# motocontro_rev_4.net
KiCad netlist of a schematic drawn in EAGLE
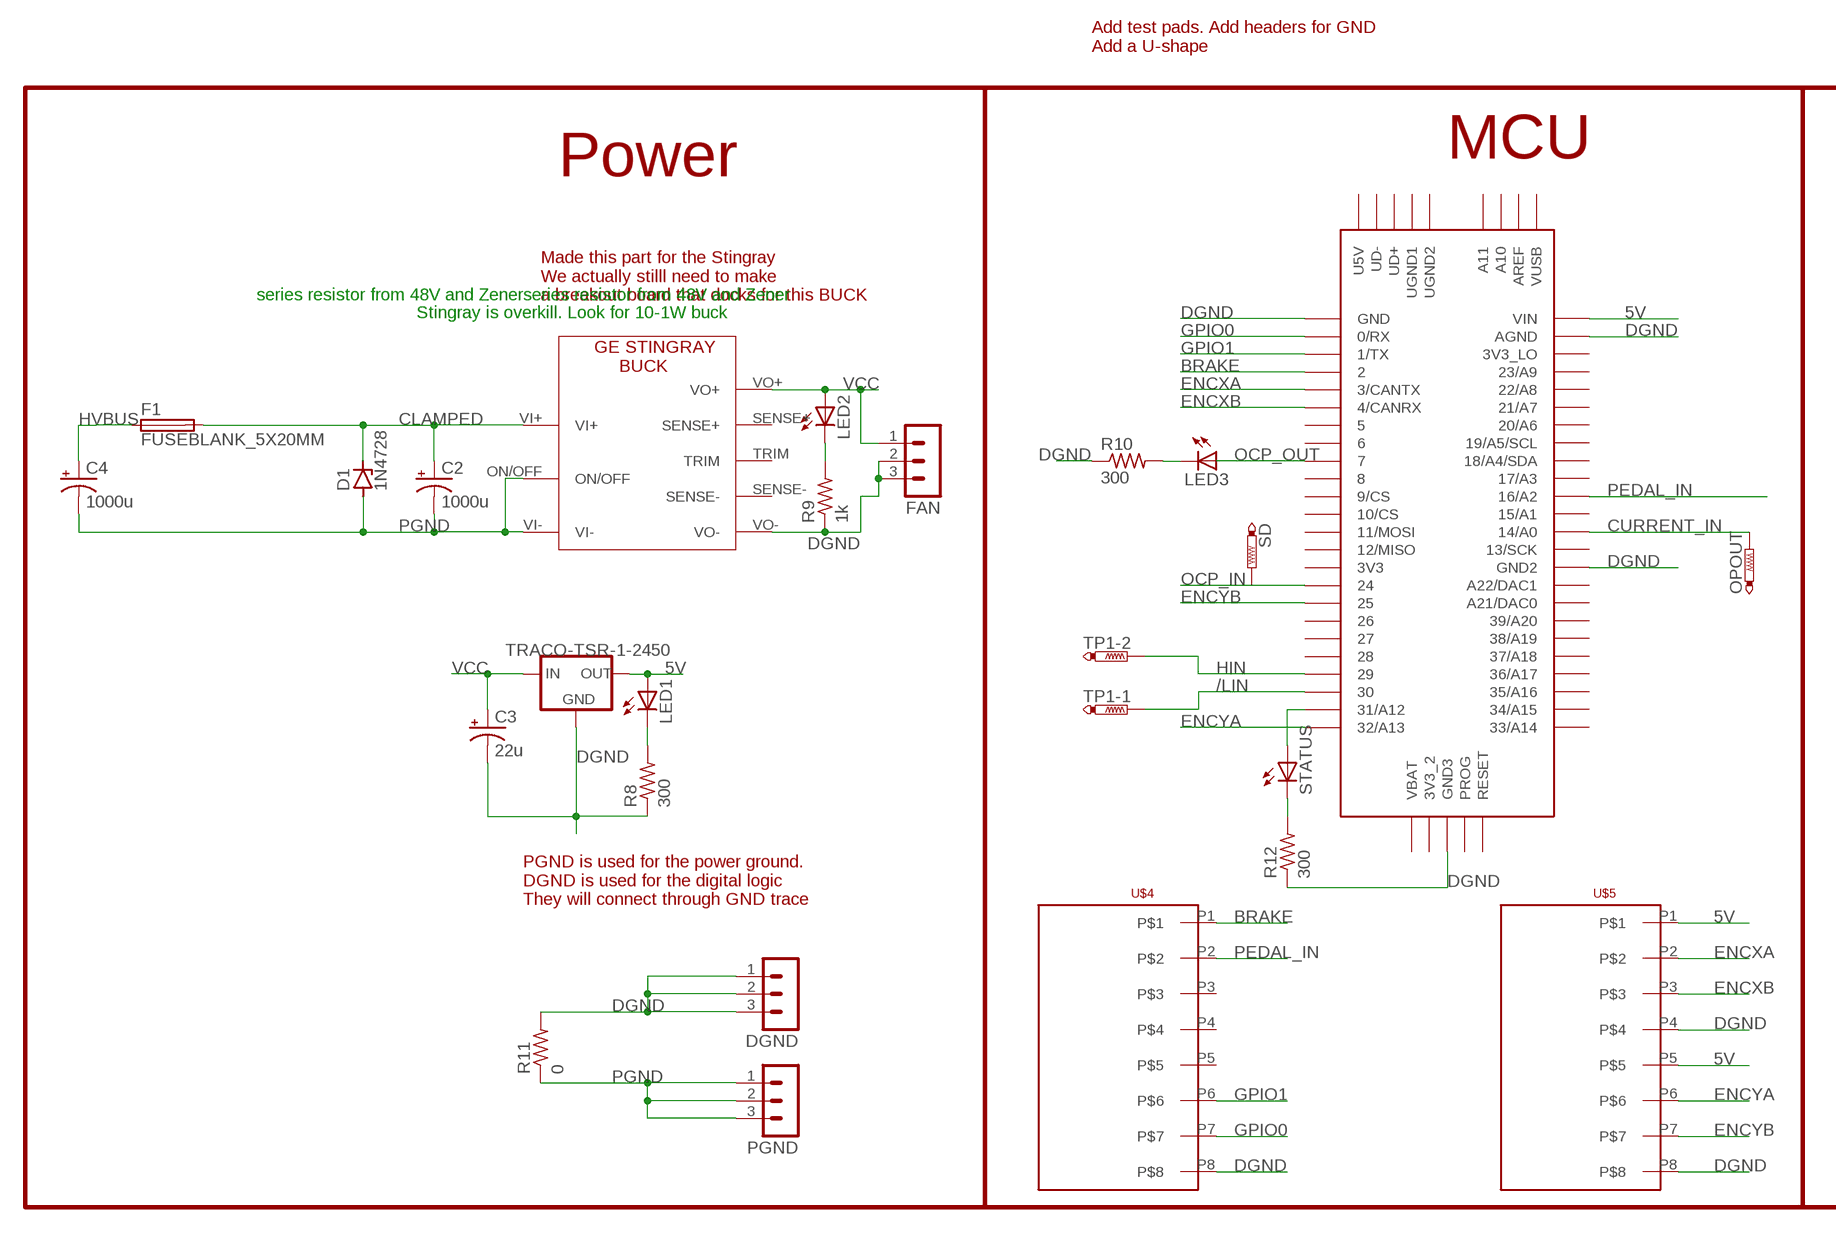
[diagram p0: schematic, sheet 1, part 1 of 2]
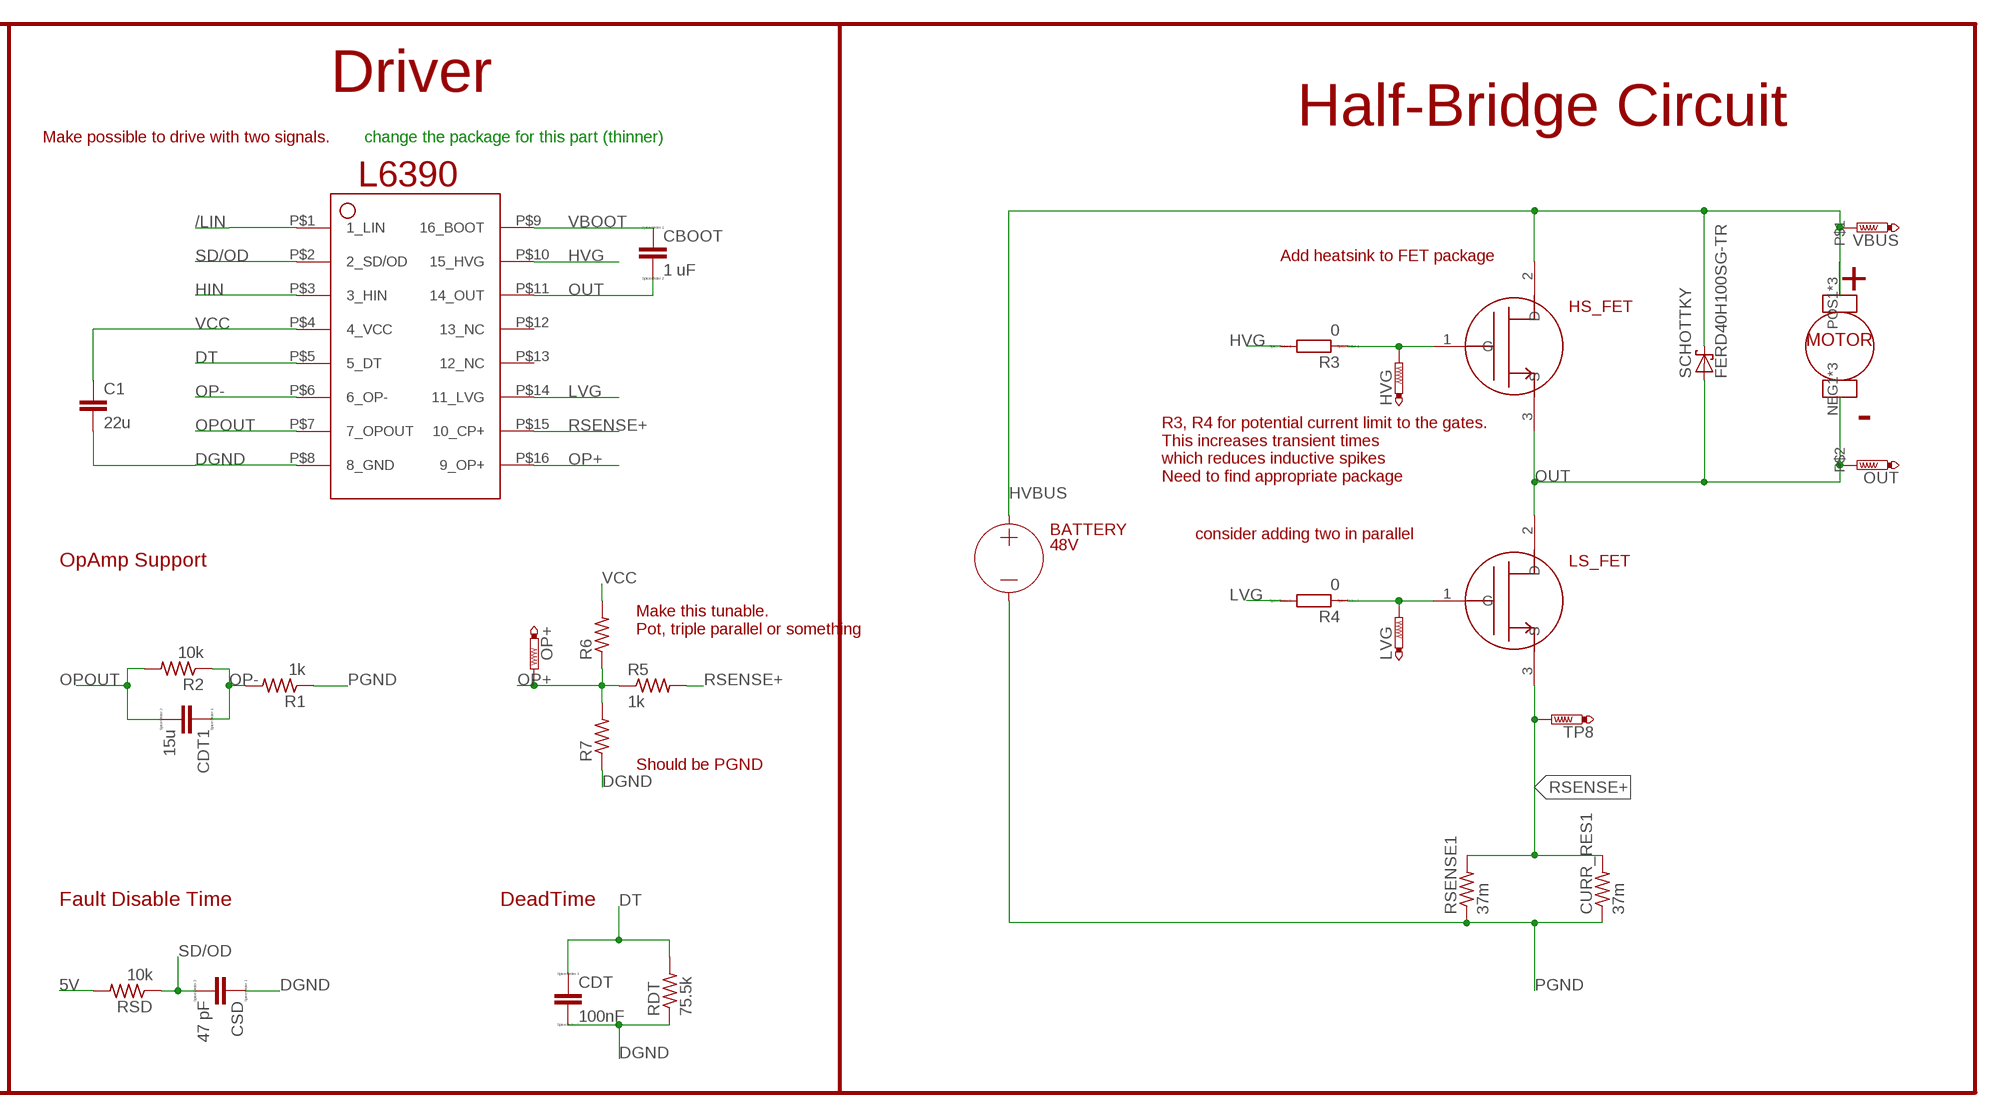
[diagram p1: schematic, sheet 1, part 2 of 2]

(export (version "E")
  (design (tool "Eeschema 10.0.6"))
  (components
    (comp (ref "BATTERY")
      (value "48V")
      (footprint "eagle-import:SB50POWER_CLAW")
      (libsource (lib "eagle-import") (part "BATTERY"))
    )
    (comp (ref "C1")
      (value "22u")
      (footprint "eagle-import:RESC0805_M")
      (libsource (lib "eagle-import") (part "CAPACITOR_0805_M"))
    )
    (comp (ref "C2")
      (value "1000u")
      (footprint "eagle-import:E5-13")
      (libsource (lib "eagle-import") (part "CPOL-USE5-13"))
    )
    (comp (ref "C3")
      (value "22u")
      (footprint "eagle-import:153CLV-0605")
      (libsource (lib "eagle-import") (part "adafruit_420_CPOL-US153CLV-0605"))
    )
    (comp (ref "C4")
      (value "1000u")
      (footprint "eagle-import:EB20D")
      (libsource (lib "eagle-import") (part "adafruit_420_CPOL-USE10-20"))
    )
    (comp (ref "CBOOT")
      (value "1 uF")
      (footprint "eagle-import:C1206")
      (libsource (lib "eagle-import") (part "CC1206"))
    )
    (comp (ref "CDT")
      (value "100nF")
      (footprint "eagle-import:C1206")
      (libsource (lib "eagle-import") (part "CC1206"))
    )
    (comp (ref "CDT1")
      (value "15u")
      (footprint "eagle-import:C1206")
      (libsource (lib "eagle-import") (part "CC1206"))
    )
    (comp (ref "CSD")
      (value "47 pF")
      (footprint "eagle-import:C1206")
      (libsource (lib "eagle-import") (part "CC1206"))
    )
    (comp (ref "CURR_RES1")
      (value "37m")
      (footprint "eagle-import:2818_WITH_VIA")
      (libsource (lib "eagle-import") (part "RESSENSE_2818"))
    )
    (comp (ref "D1")
      (value "1N4728")
      (footprint "eagle-import:DO41Z10")
      (libsource (lib "eagle-import") (part "1N4728"))
    )
    (comp (ref "DGND")
      (value "MA03-1")
      (footprint "eagle-import:MA03-1")
      (libsource (lib "eagle-import") (part "MA03-1"))
    )
    (comp (ref "F1")
      (value "FUSEBLANK_5X20MM")
      (footprint "eagle-import:FUSE_HOLDER_5X20MM")
      (libsource (lib "eagle-import") (part "FUSEBLANK_5X20MM"))
    )
    (comp (ref "FAN")
      (value "MA03-1")
      (footprint "eagle-import:MA03-1")
      (libsource (lib "eagle-import") (part "MA03-1"))
    )
    (comp (ref "HS_FET")
      (value "FDB86360_NFETTO263/D2PAK")
      (footprint "eagle-import:TO-263_D2PAK")
      (libsource (lib "eagle-import") (part "FDB86360_NFETTO263/D2PAK"))
    )
    (comp (ref "HVG")
      (value "PTR1B1,27")
      (footprint "eagle-import:B1,27")
      (libsource (lib "eagle-import") (part "PTR1B1,27"))
    )
    (comp (ref "LDO")
      (value "TRACO-TSR-1-2450")
      (footprint "eagle-import:SIP3")
      (libsource (lib "eagle-import") (part "TRACO-TSR-1-2450"))
    )
    (comp (ref "LED1")
      (value "LEDCHIP-LED0805")
      (footprint "eagle-import:CHIP-LED0805")
      (libsource (lib "eagle-import") (part "LEDCHIP-LED0805"))
    )
    (comp (ref "LED2")
      (value "LEDCHIP-LED0805")
      (footprint "eagle-import:CHIP-LED0805")
      (libsource (lib "eagle-import") (part "LEDCHIP-LED0805"))
    )
    (comp (ref "LED3")
      (value "LEDCHIP-LED0805")
      (footprint "eagle-import:CHIP-LED0805")
      (libsource (lib "eagle-import") (part "LEDCHIP-LED0805"))
    )
    (comp (ref "LS_FET")
      (value "FDB86360_NFETTO263/D2PAK")
      (footprint "eagle-import:TO-263_D2PAK")
      (libsource (lib "eagle-import") (part "FDB86360_NFETTO263/D2PAK"))
    )
    (comp (ref "LVG")
      (value "PTR1B1,27")
      (footprint "eagle-import:B1,27")
      (libsource (lib "eagle-import") (part "PTR1B1,27"))
    )
    (comp (ref "MOTOR")
      (value "MOTOR")
      (footprint "eagle-import:SB50POWER_CLAW")
      (libsource (lib "eagle-import") (part "MOTOR"))
    )
    (comp (ref "OP+")
      (value "PTR1B1,27")
      (footprint "eagle-import:B1,27")
      (libsource (lib "eagle-import") (part "PTR1B1,27"))
    )
    (comp (ref "OPOUT")
      (value "PTR1B1,27")
      (footprint "eagle-import:B1,27")
      (libsource (lib "eagle-import") (part "PTR1B1,27"))
    )
    (comp (ref "OUT")
      (value "PTR1B1,27")
      (footprint "eagle-import:B1,27")
      (libsource (lib "eagle-import") (part "PTR1B1,27"))
    )
    (comp (ref "PGND")
      (value "MA03-1")
      (footprint "eagle-import:MA03-1")
      (libsource (lib "eagle-import") (part "MA03-1"))
    )
    (comp (ref "R1")
      (value "1k")
      (footprint "eagle-import:R0805")
      (libsource (lib "eagle-import") (part "R-US_R0805"))
    )
    (comp (ref "R2")
      (value "10k")
      (footprint "eagle-import:R0805")
      (libsource (lib "eagle-import") (part "R-US_R0805"))
    )
    (comp (ref "R3")
      (value "0")
      (footprint "eagle-import:R2012")
      (libsource (lib "eagle-import") (part "RR2012"))
    )
    (comp (ref "R4")
      (value "0")
      (footprint "eagle-import:R2012")
      (libsource (lib "eagle-import") (part "RR2012"))
    )
    (comp (ref "R5")
      (value "1k")
      (footprint "eagle-import:R0805")
      (libsource (lib "eagle-import") (part "R-US_R0805"))
    )
    (comp (ref "R6")
      (value "R-US_R0805")
      (footprint "eagle-import:R0805")
      (libsource (lib "eagle-import") (part "R-US_R0805"))
    )
    (comp (ref "R7")
      (value "R-US_R0805")
      (footprint "eagle-import:R0805")
      (libsource (lib "eagle-import") (part "R-US_R0805"))
    )
    (comp (ref "R8")
      (value "300")
      (footprint "eagle-import:R0805")
      (libsource (lib "eagle-import") (part "R-US_R0805"))
    )
    (comp (ref "R9")
      (value "1k")
      (footprint "eagle-import:R0805")
      (libsource (lib "eagle-import") (part "R-US_R0805"))
    )
    (comp (ref "R10")
      (value "300")
      (footprint "eagle-import:R0805")
      (libsource (lib "eagle-import") (part "R-US_R0805"))
    )
    (comp (ref "R11")
      (value "0")
      (footprint "eagle-import:R0805")
      (libsource (lib "eagle-import") (part "R-US_R0805"))
    )
    (comp (ref "R12")
      (value "300")
      (footprint "eagle-import:R0805")
      (libsource (lib "eagle-import") (part "R-US_R0805"))
    )
    (comp (ref "RDT")
      (value "75.5k")
      (footprint "eagle-import:R0805")
      (libsource (lib "eagle-import") (part "R-US_R0805"))
    )
    (comp (ref "RSD")
      (value "10k")
      (footprint "eagle-import:R0805")
      (libsource (lib "eagle-import") (part "R-US_R0805"))
    )
    (comp (ref "RSENSE1")
      (value "37m")
      (footprint "eagle-import:2818_WITH_VIA")
      (libsource (lib "eagle-import") (part "RESSENSE_2818"))
    )
    (comp (ref "SCHOTTKY")
      (value "FERD40H100SG-TR")
      (footprint "eagle-import:TO-263_D2PAK")
      (libsource (lib "eagle-import") (part "FERD40H100SG-TR"))
    )
    (comp (ref "SD")
      (value "PTR1B1,27")
      (footprint "eagle-import:B1,27")
      (libsource (lib "eagle-import") (part "PTR1B1,27"))
    )
    (comp (ref "STATUS")
      (value "LEDCHIP-LED0805")
      (footprint "eagle-import:CHIP-LED0805")
      (libsource (lib "eagle-import") (part "LEDCHIP-LED0805"))
    )
    (comp (ref "TP1")
      (value "PTR2")
      (footprint "eagle-import:P2-38-17")
      (libsource (lib "eagle-import") (part "PTR2"))
    )
    (comp (ref "TP8")
      (value "PTR1B1,27")
      (footprint "eagle-import:B1,27")
      (libsource (lib "eagle-import") (part "PTR1B1,27"))
    )
    (comp (ref "U$1")
      (value "L6390SO-16NARRROW")
      (footprint "eagle-import:SO-16NARROW")
      (libsource (lib "eagle-import") (part "L6390SO-16NARRROW"))
    )
    (comp (ref "U$2")
      (value "TEENSY_3.5/3.6")
      (footprint "eagle-import:TEENSY_3.5_3.6")
      (libsource (lib "eagle-import") (part "TEENSY_3.5/3.6"))
    )
    (comp (ref "U$3")
      (value "GE_STINGRAY_H")
      (footprint "eagle-import:GE_STINGRAY")
      (libsource (lib "eagle-import") (part "GE_STINGRAY_H"))
    )
    (comp (ref "U$4")
      (value "8-PIN-MOLEX-RA-FEMALE")
      (footprint "eagle-import:8-PIN-MOLEX")
      (libsource (lib "eagle-import") (part "8-PIN-MOLEX-RA-FEMALE"))
    )
    (comp (ref "U$5")
      (value "8-PIN-MOLEX-RA-FEMALE")
      (footprint "eagle-import:8-PIN-MOLEX")
      (libsource (lib "eagle-import") (part "8-PIN-MOLEX-RA-FEMALE"))
    )
    (comp (ref "VBUS")
      (value "PTR1B1,27")
      (footprint "eagle-import:B1,27")
      (libsource (lib "eagle-import") (part "PTR1B1,27"))
    )
  )
  (nets
    (net (code "1") (name "/5V") (class "Default")
      (node (ref "LDO") (pin "3") (pinfunction "OUT_3") (pintype "passive"))
      (node (ref "LED1") (pin "A") (pinfunction "A_A") (pintype "passive"))
      (node (ref "RSD") (pin "2") (pinfunction "2_2") (pintype "passive"))
      (node (ref "U$2") (pin "VIN") (pinfunction "VIN_VIN") (pintype "bidirectional"))
      (node (ref "U$5") (pin "P1") (pinfunction "P$1_P1") (pintype "bidirectional"))
      (node (ref "U$5") (pin "P5") (pinfunction "P$5_P5") (pintype "bidirectional"))
    )
    (net (code "2") (name "/BRAKE") (class "Default")
      (node (ref "U$2") (pin "2") (pinfunction "2_2") (pintype "bidirectional"))
      (node (ref "U$4") (pin "P1") (pinfunction "P$1_P1") (pintype "bidirectional"))
    )
    (net (code "3") (name "/CLAMPED") (class "Default")
      (node (ref "C2") (pin "+") (pinfunction "+_+") (pintype "passive"))
      (node (ref "D1") (pin "C") (pinfunction "C_C") (pintype "passive"))
      (node (ref "F1") (pin "2") (pinfunction "2_2") (pintype "passive"))
      (node (ref "U$3") (pin "VI+") (pinfunction "VI+_VI+") (pintype "bidirectional"))
    )
    (net (code "4") (name "/CURRENT_IN") (class "Default")
      (node (ref "OPOUT") (pin "TP") (pinfunction "TP_TP") (pintype "input"))
      (node (ref "U$2") (pin "14/A0") (pinfunction "14/A0_14/A0") (pintype "bidirectional"))
    )
    (net (code "5") (name "/DGND") (class "Default")
      (node (ref "C1") (pin "2") (pinfunction "2_2") (pintype "passive"))
      (node (ref "C3") (pin "-") (pinfunction "-_-") (pintype "passive"))
      (node (ref "CDT") (pin "2") (pinfunction "2_2") (pintype "passive"))
      (node (ref "CSD") (pin "1") (pinfunction "1_1") (pintype "passive"))
      (node (ref "DGND") (pin "1") (pinfunction "1_1") (pintype "passive"))
      (node (ref "DGND") (pin "2") (pinfunction "2_2") (pintype "passive"))
      (node (ref "DGND") (pin "3") (pinfunction "3_3") (pintype "passive"))
      (node (ref "FAN") (pin "2") (pinfunction "2_2") (pintype "passive"))
      (node (ref "FAN") (pin "3") (pinfunction "3_3") (pintype "passive"))
      (node (ref "LDO") (pin "2") (pinfunction "GND_2") (pintype "input"))
      (node (ref "R10") (pin "1") (pinfunction "1_1") (pintype "passive"))
      (node (ref "R11") (pin "2") (pinfunction "2_2") (pintype "passive"))
      (node (ref "R12") (pin "1") (pinfunction "1_1") (pintype "passive"))
      (node (ref "R7") (pin "1") (pinfunction "1_1") (pintype "passive"))
      (node (ref "R8") (pin "1") (pinfunction "1_1") (pintype "passive"))
      (node (ref "R9") (pin "1") (pinfunction "1_1") (pintype "passive"))
      (node (ref "RDT") (pin "1") (pinfunction "1_1") (pintype "passive"))
      (node (ref "U$1") (pin "P$8") (pinfunction "8_GND_P$8") (pintype "bidirectional"))
      (node (ref "U$2") (pin "AGND") (pinfunction "AGND_AGND") (pintype "bidirectional"))
      (node (ref "U$2") (pin "GND") (pinfunction "GND_GND") (pintype "bidirectional"))
      (node (ref "U$2") (pin "GND2") (pinfunction "GND2_GND2") (pintype "bidirectional"))
      (node (ref "U$2") (pin "GND3") (pinfunction "GND3_GND3") (pintype "bidirectional"))
      (node (ref "U$3") (pin "VO-") (pinfunction "VO-_VO-") (pintype "bidirectional"))
      (node (ref "U$4") (pin "P8") (pinfunction "P$8_P8") (pintype "bidirectional"))
      (node (ref "U$5") (pin "P4") (pinfunction "P$4_P4") (pintype "bidirectional"))
      (node (ref "U$5") (pin "P8") (pinfunction "P$8_P8") (pintype "bidirectional"))
    )
    (net (code "6") (name "/DT") (class "Default")
      (node (ref "CDT") (pin "1") (pinfunction "1_1") (pintype "passive"))
      (node (ref "RDT") (pin "2") (pinfunction "2_2") (pintype "passive"))
      (node (ref "U$1") (pin "P$5") (pinfunction "5_DT_P$5") (pintype "bidirectional"))
    )
    (net (code "7") (name "/ENCXA") (class "Default")
      (node (ref "U$2") (pin "3/CANTX") (pinfunction "3/CANTX_3/CANTX") (pintype "bidirectional"))
      (node (ref "U$5") (pin "P2") (pinfunction "P$2_P2") (pintype "bidirectional"))
    )
    (net (code "8") (name "/ENCXB") (class "Default")
      (node (ref "U$2") (pin "4/CANRX") (pinfunction "4/CANRX_4/CANRX") (pintype "bidirectional"))
      (node (ref "U$5") (pin "P3") (pinfunction "P$3_P3") (pintype "bidirectional"))
    )
    (net (code "9") (name "/ENCYA") (class "Default")
      (node (ref "U$2") (pin "32/A13") (pinfunction "32/A13_32/A13") (pintype "bidirectional"))
      (node (ref "U$5") (pin "P6") (pinfunction "P$6_P6") (pintype "bidirectional"))
    )
    (net (code "10") (name "/ENCYB") (class "Default")
      (node (ref "U$2") (pin "25") (pinfunction "25_25") (pintype "bidirectional"))
      (node (ref "U$5") (pin "P7") (pinfunction "P$7_P7") (pintype "bidirectional"))
    )
    (net (code "11") (name "/GPIO0") (class "Default")
      (node (ref "U$2") (pin "0/RX") (pinfunction "0/RX_0/RX") (pintype "bidirectional"))
      (node (ref "U$4") (pin "P7") (pinfunction "P$7_P7") (pintype "bidirectional"))
    )
    (net (code "12") (name "/GPIO1") (class "Default")
      (node (ref "U$2") (pin "1/TX") (pinfunction "1/TX_1/TX") (pintype "bidirectional"))
      (node (ref "U$4") (pin "P6") (pinfunction "P$6_P6") (pintype "bidirectional"))
    )
    (net (code "13") (name "/HIN") (class "Default")
      (node (ref "TP1") (pin "TP-2") (pinfunction "TP_TP-2") (pintype "input"))
      (node (ref "U$1") (pin "P$3") (pinfunction "3_HIN_P$3") (pintype "bidirectional"))
      (node (ref "U$2") (pin "29") (pinfunction "29_29") (pintype "bidirectional"))
    )
    (net (code "14") (name "/HVBUS") (class "Default")
      (node (ref "BATTERY") (pin "POS1") (pinfunction "+_POS1") (pintype "passive"))
      (node (ref "BATTERY") (pin "POS2") (pinfunction "+_POS2") (pintype "passive"))
      (node (ref "BATTERY") (pin "POS3") (pinfunction "+_POS3") (pintype "passive"))
      (node (ref "C4") (pin "+") (pinfunction "+_+") (pintype "passive"))
      (node (ref "F1") (pin "1") (pinfunction "1_1") (pintype "passive"))
      (node (ref "HS_FET") (pin "2") (pinfunction "D_2") (pintype "bidirectional"))
      (node (ref "MOTOR") (pin "POS1") (pinfunction "P$1_POS1") (pintype "bidirectional"))
      (node (ref "MOTOR") (pin "POS2") (pinfunction "P$1_POS2") (pintype "bidirectional"))
      (node (ref "MOTOR") (pin "POS3") (pinfunction "P$1_POS3") (pintype "bidirectional"))
      (node (ref "SCHOTTKY") (pin "2") (pinfunction "C_2") (pintype "passive"))
      (node (ref "VBUS") (pin "TP") (pinfunction "TP_TP") (pintype "input"))
    )
    (net (code "15") (name "/HVG") (class "Default")
      (node (ref "R3") (pin "2") (pinfunction "2_2") (pintype "passive"))
      (node (ref "U$1") (pin "P$10") (pinfunction "15_HVG_P$10") (pintype "bidirectional"))
    )
    (net (code "16") (name "/LVG") (class "Default")
      (node (ref "R4") (pin "2") (pinfunction "2_2") (pintype "passive"))
      (node (ref "U$1") (pin "P$14") (pinfunction "11_LVG_P$14") (pintype "bidirectional"))
    )
    (net (code "17") (name "/OCP_IN") (class "Default")
      (node (ref "SD") (pin "TP") (pinfunction "TP_TP") (pintype "input"))
      (node (ref "U$2") (pin "24") (pinfunction "24_24") (pintype "bidirectional"))
    )
    (net (code "18") (name "/OCP_OUT") (class "Default")
      (node (ref "LED3") (pin "A") (pinfunction "A_A") (pintype "passive"))
      (node (ref "U$2") (pin "7") (pinfunction "7_7") (pintype "bidirectional"))
    )
    (net (code "19") (name "/OP+") (class "Default")
      (node (ref "OP+") (pin "TP") (pinfunction "TP_TP") (pintype "input"))
      (node (ref "R5") (pin "1") (pinfunction "1_1") (pintype "passive"))
      (node (ref "R6") (pin "1") (pinfunction "1_1") (pintype "passive"))
      (node (ref "R7") (pin "2") (pinfunction "2_2") (pintype "passive"))
      (node (ref "U$1") (pin "P$16") (pinfunction "9_OP+_P$16") (pintype "bidirectional"))
    )
    (net (code "20") (name "/OP-") (class "Default")
      (node (ref "CDT1") (pin "1") (pinfunction "1_1") (pintype "passive"))
      (node (ref "R1") (pin "2") (pinfunction "2_2") (pintype "passive"))
      (node (ref "R2") (pin "1") (pinfunction "1_1") (pintype "passive"))
      (node (ref "U$1") (pin "P$6") (pinfunction "6_OP-_P$6") (pintype "bidirectional"))
    )
    (net (code "21") (name "/OPOUT") (class "Default")
      (node (ref "CDT1") (pin "2") (pinfunction "2_2") (pintype "passive"))
      (node (ref "R2") (pin "2") (pinfunction "2_2") (pintype "passive"))
      (node (ref "U$1") (pin "P$7") (pinfunction "7_OPOUT_P$7") (pintype "bidirectional"))
    )
    (net (code "22") (name "/OUT") (class "Default")
      (node (ref "CBOOT") (pin "2") (pinfunction "2_2") (pintype "passive"))
      (node (ref "HS_FET") (pin "3") (pinfunction "S_3") (pintype "bidirectional"))
      (node (ref "LS_FET") (pin "2") (pinfunction "D_2") (pintype "bidirectional"))
      (node (ref "MOTOR") (pin "NEG1") (pinfunction "P$2_NEG1") (pintype "bidirectional"))
      (node (ref "MOTOR") (pin "NEG2") (pinfunction "P$2_NEG2") (pintype "bidirectional"))
      (node (ref "MOTOR") (pin "NEG3") (pinfunction "P$2_NEG3") (pintype "bidirectional"))
      (node (ref "OUT") (pin "TP") (pinfunction "TP_TP") (pintype "input"))
      (node (ref "SCHOTTKY") (pin "3") (pinfunction "A_3") (pintype "passive"))
      (node (ref "U$1") (pin "P$11") (pinfunction "14_OUT_P$11") (pintype "bidirectional"))
    )
    (net (code "23") (name "/PEDAL_IN") (class "Default")
      (node (ref "U$2") (pin "16/A2") (pinfunction "16/A2_16/A2") (pintype "bidirectional"))
      (node (ref "U$4") (pin "P2") (pinfunction "P$2_P2") (pintype "bidirectional"))
    )
    (net (code "24") (name "/PGND") (class "Default")
      (node (ref "BATTERY") (pin "NEG1") (pinfunction "-_NEG1") (pintype "passive"))
      (node (ref "BATTERY") (pin "NEG2") (pinfunction "-_NEG2") (pintype "passive"))
      (node (ref "BATTERY") (pin "NEG3") (pinfunction "-_NEG3") (pintype "passive"))
      (node (ref "C2") (pin "-") (pinfunction "-_-") (pintype "passive"))
      (node (ref "C4") (pin "-") (pinfunction "-_-") (pintype "passive"))
      (node (ref "CURR_RES1") (pin "P$1") (pinfunction "1_P$1") (pintype "passive"))
      (node (ref "CURR_RES1") (pin "P1.1") (pinfunction "1_P1.1") (pintype "passive"))
      (node (ref "D1") (pin "A") (pinfunction "A_A") (pintype "passive"))
      (node (ref "PGND") (pin "1") (pinfunction "1_1") (pintype "passive"))
      (node (ref "PGND") (pin "2") (pinfunction "2_2") (pintype "passive"))
      (node (ref "PGND") (pin "3") (pinfunction "3_3") (pintype "passive"))
      (node (ref "R1") (pin "1") (pinfunction "1_1") (pintype "passive"))
      (node (ref "R11") (pin "1") (pinfunction "1_1") (pintype "passive"))
      (node (ref "RSENSE1") (pin "P$1") (pinfunction "1_P$1") (pintype "passive"))
      (node (ref "RSENSE1") (pin "P1.1") (pinfunction "1_P1.1") (pintype "passive"))
      (node (ref "U$3") (pin "ON/OFF") (pinfunction "ON/OFF_ON/OFF") (pintype "bidirectional"))
      (node (ref "U$3") (pin "VI-") (pinfunction "VI-_VI-") (pintype "bidirectional"))
    )
    (net (code "25") (name "/SD{slash}OD") (class "Default")
      (node (ref "CSD") (pin "2") (pinfunction "2_2") (pintype "passive"))
      (node (ref "RSD") (pin "1") (pinfunction "1_1") (pintype "passive"))
      (node (ref "U$1") (pin "P$2") (pinfunction "2_SD/OD_P$2") (pintype "bidirectional"))
    )
    (net (code "26") (name "/VBOOT") (class "Default")
      (node (ref "CBOOT") (pin "1") (pinfunction "1_1") (pintype "passive"))
      (node (ref "U$1") (pin "P$9") (pinfunction "16_BOOT_P$9") (pintype "bidirectional"))
    )
    (net (code "27") (name "/VCC") (class "Default")
      (node (ref "C1") (pin "1") (pinfunction "1_1") (pintype "passive"))
      (node (ref "C3") (pin "+") (pinfunction "+_+") (pintype "passive"))
      (node (ref "FAN") (pin "1") (pinfunction "1_1") (pintype "passive"))
      (node (ref "LDO") (pin "1") (pinfunction "IN_1") (pintype "input"))
      (node (ref "LED2") (pin "A") (pinfunction "A_A") (pintype "passive"))
      (node (ref "R6") (pin "2") (pinfunction "2_2") (pintype "passive"))
      (node (ref "U$1") (pin "P$4") (pinfunction "4_VCC_P$4") (pintype "bidirectional"))
      (node (ref "U$3") (pin "VO+") (pinfunction "VO+_VO+") (pintype "bidirectional"))
    )
    (net (code "28") (name "/{slash}LIN") (class "Default")
      (node (ref "TP1") (pin "TP-1") (pinfunction "TP_TP-1") (pintype "input"))
      (node (ref "U$1") (pin "P$1") (pinfunction "1_LIN_P$1") (pintype "bidirectional"))
      (node (ref "U$2") (pin "30") (pinfunction "30_30") (pintype "bidirectional"))
    )
    (net (code "29") (name "Net-(HS_FET-G)") (class "Default")
      (node (ref "HS_FET") (pin "1") (pinfunction "G_1") (pintype "bidirectional"))
      (node (ref "HVG") (pin "TP") (pinfunction "TP_TP") (pintype "input"))
      (node (ref "R3") (pin "1") (pinfunction "1_1") (pintype "passive"))
    )
    (net (code "30") (name "Net-(LED1-PadC)") (class "Default")
      (node (ref "LED1") (pin "C") (pinfunction "C_C") (pintype "passive"))
      (node (ref "R8") (pin "2") (pinfunction "2_2") (pintype "passive"))
    )
    (net (code "31") (name "Net-(LED2-PadC)") (class "Default")
      (node (ref "LED2") (pin "C") (pinfunction "C_C") (pintype "passive"))
      (node (ref "R9") (pin "2") (pinfunction "2_2") (pintype "passive"))
    )
    (net (code "32") (name "Net-(LED3-PadC)") (class "Default")
      (node (ref "LED3") (pin "C") (pinfunction "C_C") (pintype "passive"))
      (node (ref "R10") (pin "2") (pinfunction "2_2") (pintype "passive"))
    )
    (net (code "33") (name "Net-(LS_FET-G)") (class "Default")
      (node (ref "LS_FET") (pin "1") (pinfunction "G_1") (pintype "bidirectional"))
      (node (ref "LVG") (pin "TP") (pinfunction "TP_TP") (pintype "input"))
      (node (ref "R4") (pin "1") (pinfunction "1_1") (pintype "passive"))
    )
    (net (code "34") (name "Net-(R12-Pad2)") (class "Default")
      (node (ref "R12") (pin "2") (pinfunction "2_2") (pintype "passive"))
      (node (ref "STATUS") (pin "C") (pinfunction "C_C") (pintype "passive"))
    )
    (net (code "35") (name "Net-(STATUS-PadA)") (class "Default")
      (node (ref "STATUS") (pin "A") (pinfunction "A_A") (pintype "passive"))
      (node (ref "U$2") (pin "31/A12") (pinfunction "31/A12_31/A12") (pintype "bidirectional"))
    )
    (net (code "36") (name "RSENSE+") (class "Default")
      (node (ref "CURR_RES1") (pin "P$2") (pinfunction "2_P$2") (pintype "passive"))
      (node (ref "CURR_RES1") (pin "P2.2") (pinfunction "2_P2.2") (pintype "passive"))
      (node (ref "LS_FET") (pin "3") (pinfunction "S_3") (pintype "bidirectional"))
      (node (ref "R5") (pin "2") (pinfunction "2_2") (pintype "passive"))
      (node (ref "RSENSE1") (pin "P$2") (pinfunction "2_P$2") (pintype "passive"))
      (node (ref "RSENSE1") (pin "P2.2") (pinfunction "2_P2.2") (pintype "passive"))
      (node (ref "TP8") (pin "TP") (pinfunction "TP_TP") (pintype "input"))
      (node (ref "U$1") (pin "P$15") (pinfunction "10_CP+_P$15") (pintype "bidirectional"))
    )
    (net (code "37") (name "unconnected-(U$1-12_NC-PadP$13)") (class "Default")
      (node (ref "U$1") (pin "P$13") (pinfunction "12_NC_P$13") (pintype "bidirectional"))
    )
    (net (code "38") (name "unconnected-(U$1-13_NC-PadP$12)") (class "Default")
      (node (ref "U$1") (pin "P$12") (pinfunction "13_NC_P$12") (pintype "bidirectional"))
    )
    (net (code "39") (name "unconnected-(U$2-A21{slash}DAC0-Pad21{slash}DAC0)") (class "Default")
      (node (ref "U$2") (pin "21/DAC0") (pinfunction "A21/DAC0_21/DAC0") (pintype "bidirectional"))
    )
    (net (code "40") (name "unconnected-(U$2-Pad3V3)") (class "Default")
      (node (ref "U$2") (pin "3V3") (pinfunction "3V3_3V3") (pintype "bidirectional"))
    )
    (net (code "41") (name "unconnected-(U$2-Pad3V3_2)") (class "Default")
      (node (ref "U$2") (pin "3V3_2") (pinfunction "3V3_2_3V3_2") (pintype "bidirectional"))
    )
    (net (code "42") (name "unconnected-(U$2-Pad3V3_LO)") (class "Default")
      (node (ref "U$2") (pin "3V3_LO") (pinfunction "3V3_LO_3V3_LO") (pintype "bidirectional"))
    )
    (net (code "43") (name "unconnected-(U$2-Pad5)") (class "Default")
      (node (ref "U$2") (pin "5") (pinfunction "5_5") (pintype "bidirectional"))
    )
    (net (code "44") (name "unconnected-(U$2-Pad6)") (class "Default")
      (node (ref "U$2") (pin "6") (pinfunction "6_6") (pintype "bidirectional"))
    )
    (net (code "45") (name "unconnected-(U$2-Pad8)") (class "Default")
      (node (ref "U$2") (pin "8") (pinfunction "8_8") (pintype "bidirectional"))
    )
    (net (code "46") (name "unconnected-(U$2-Pad9{slash}CS)") (class "Default")
      (node (ref "U$2") (pin "9/CS") (pinfunction "9/CS_9/CS") (pintype "bidirectional"))
    )
    (net (code "47") (name "unconnected-(U$2-Pad10{slash}CS)") (class "Default")
      (node (ref "U$2") (pin "10/CS") (pinfunction "10/CS_10/CS") (pintype "bidirectional"))
    )
    (net (code "48") (name "unconnected-(U$2-Pad11{slash}MOSI)") (class "Default")
      (node (ref "U$2") (pin "11/MOSI") (pinfunction "11/MOSI_11/MOSI") (pintype "bidirectional"))
    )
    (net (code "49") (name "unconnected-(U$2-Pad12{slash}MISO)") (class "Default")
      (node (ref "U$2") (pin "12/MISO") (pinfunction "12/MISO_12/MISO") (pintype "bidirectional"))
    )
    (net (code "50") (name "unconnected-(U$2-Pad13{slash}SCK)") (class "Default")
      (node (ref "U$2") (pin "13/SCK") (pinfunction "13/SCK_13/SCK") (pintype "bidirectional"))
    )
    (net (code "51") (name "unconnected-(U$2-Pad15{slash}A1)") (class "Default")
      (node (ref "U$2") (pin "15/A1") (pinfunction "15/A1_15/A1") (pintype "bidirectional"))
    )
    (net (code "52") (name "unconnected-(U$2-Pad17{slash}A3)") (class "Default")
      (node (ref "U$2") (pin "17/A3") (pinfunction "17/A3_17/A3") (pintype "bidirectional"))
    )
    (net (code "53") (name "unconnected-(U$2-Pad18{slash}A4{slash}SDA)") (class "Default")
      (node (ref "U$2") (pin "18/A4/SDA") (pinfunction "18/A4/SDA_18/A4/SDA") (pintype "bidirectional"))
    )
    (net (code "54") (name "unconnected-(U$2-Pad19{slash}A5{slash}SCL)") (class "Default")
      (node (ref "U$2") (pin "19/A5/SCL") (pinfunction "19/A5/SCL_19/A5/SCL") (pintype "bidirectional"))
    )
    (net (code "55") (name "unconnected-(U$2-Pad20{slash}A6)") (class "Default")
      (node (ref "U$2") (pin "20/A6") (pinfunction "20/A6_20/A6") (pintype "bidirectional"))
    )
    (net (code "56") (name "unconnected-(U$2-Pad21{slash}A7)") (class "Default")
      (node (ref "U$2") (pin "21/A7") (pinfunction "21/A7_21/A7") (pintype "bidirectional"))
    )
    (net (code "57") (name "unconnected-(U$2-Pad22{slash}A8)") (class "Default")
      (node (ref "U$2") (pin "22/A8") (pinfunction "22/A8_22/A8") (pintype "bidirectional"))
    )
    (net (code "58") (name "unconnected-(U$2-Pad23{slash}A9)") (class "Default")
      (node (ref "U$2") (pin "23/A9") (pinfunction "23/A9_23/A9") (pintype "bidirectional"))
    )
    (net (code "59") (name "unconnected-(U$2-Pad26)") (class "Default")
      (node (ref "U$2") (pin "26") (pinfunction "26_26") (pintype "bidirectional"))
    )
    (net (code "60") (name "unconnected-(U$2-Pad27)") (class "Default")
      (node (ref "U$2") (pin "27") (pinfunction "27_27") (pintype "bidirectional"))
    )
    (net (code "61") (name "unconnected-(U$2-Pad28)") (class "Default")
      (node (ref "U$2") (pin "28") (pinfunction "28_28") (pintype "bidirectional"))
    )
    (net (code "62") (name "unconnected-(U$2-Pad33{slash}A14)") (class "Default")
      (node (ref "U$2") (pin "33/A14") (pinfunction "33/A14_33/A14") (pintype "bidirectional"))
    )
    (net (code "63") (name "unconnected-(U$2-Pad34{slash}A15)") (class "Default")
      (node (ref "U$2") (pin "34/A15") (pinfunction "34/A15_34/A15") (pintype "bidirectional"))
    )
    (net (code "64") (name "unconnected-(U$2-Pad35{slash}A16)") (class "Default")
      (node (ref "U$2") (pin "35/A16") (pinfunction "35/A16_35/A16") (pintype "bidirectional"))
    )
    (net (code "65") (name "unconnected-(U$2-Pad36{slash}A17)") (class "Default")
      (node (ref "U$2") (pin "36/A17") (pinfunction "36/A17_36/A17") (pintype "bidirectional"))
    )
    (net (code "66") (name "unconnected-(U$2-Pad37{slash}A18)") (class "Default")
      (node (ref "U$2") (pin "37/A18") (pinfunction "37/A18_37/A18") (pintype "bidirectional"))
    )
    (net (code "67") (name "unconnected-(U$2-Pad38{slash}A19)") (class "Default")
      (node (ref "U$2") (pin "38/A19") (pinfunction "38/A19_38/A19") (pintype "bidirectional"))
    )
    (net (code "68") (name "unconnected-(U$2-Pad39{slash}A20)") (class "Default")
      (node (ref "U$2") (pin "39/A20") (pinfunction "39/A20_39/A20") (pintype "bidirectional"))
    )
    (net (code "69") (name "unconnected-(U$2-PadA10)") (class "Default")
      (node (ref "U$2") (pin "A10") (pinfunction "A10_A10") (pintype "bidirectional"))
    )
    (net (code "70") (name "unconnected-(U$2-PadA11)") (class "Default")
      (node (ref "U$2") (pin "A11") (pinfunction "A11_A11") (pintype "bidirectional"))
    )
    (net (code "71") (name "unconnected-(U$2-PadA22{slash}DAC1)") (class "Default")
      (node (ref "U$2") (pin "A22/DAC1") (pinfunction "A22/DAC1_A22/DAC1") (pintype "bidirectional"))
    )
    (net (code "72") (name "unconnected-(U$2-PadAREF)") (class "Default")
      (node (ref "U$2") (pin "AREF") (pinfunction "AREF_AREF") (pintype "bidirectional"))
    )
    (net (code "73") (name "unconnected-(U$2-PadPROG)") (class "Default")
      (node (ref "U$2") (pin "PROG") (pinfunction "PROG_PROG") (pintype "bidirectional"))
    )
    (net (code "74") (name "unconnected-(U$2-PadRESET)") (class "Default")
      (node (ref "U$2") (pin "RESET") (pinfunction "RESET_RESET") (pintype "bidirectional"))
    )
    (net (code "75") (name "unconnected-(U$2-PadU5V)") (class "Default")
      (node (ref "U$2") (pin "U5V") (pinfunction "U5V_U5V") (pintype "bidirectional"))
    )
    (net (code "76") (name "unconnected-(U$2-PadUD+)") (class "Default")
      (node (ref "U$2") (pin "UD+") (pinfunction "UD+_UD+") (pintype "bidirectional"))
    )
    (net (code "77") (name "unconnected-(U$2-PadUD-)") (class "Default")
      (node (ref "U$2") (pin "UD-") (pinfunction "UD-_UD-") (pintype "bidirectional"))
    )
    (net (code "78") (name "unconnected-(U$2-PadUGND1)") (class "Default")
      (node (ref "U$2") (pin "UGND1") (pinfunction "UGND1_UGND1") (pintype "bidirectional"))
    )
    (net (code "79") (name "unconnected-(U$2-PadUGND2)") (class "Default")
      (node (ref "U$2") (pin "UGND2") (pinfunction "UGND2_UGND2") (pintype "bidirectional"))
    )
    (net (code "80") (name "unconnected-(U$2-PadVBAT)") (class "Default")
      (node (ref "U$2") (pin "VBAT") (pinfunction "VBAT_VBAT") (pintype "bidirectional"))
    )
    (net (code "81") (name "unconnected-(U$2-PadVUSB)") (class "Default")
      (node (ref "U$2") (pin "VUSB") (pinfunction "VUSB_VUSB") (pintype "bidirectional"))
    )
    (net (code "82") (name "unconnected-(U$3-PadSENSE+)") (class "Default")
      (node (ref "U$3") (pin "SENSE+") (pinfunction "SENSE+_SENSE+") (pintype "bidirectional"))
    )
    (net (code "83") (name "unconnected-(U$3-PadSENSE-)") (class "Default")
      (node (ref "U$3") (pin "SENSE-") (pinfunction "SENSE-_SENSE-") (pintype "bidirectional"))
    )
    (net (code "84") (name "unconnected-(U$3-PadTRIM)") (class "Default")
      (node (ref "U$3") (pin "TRIM") (pinfunction "TRIM_TRIM") (pintype "bidirectional"))
    )
    (net (code "85") (name "unconnected-(U$4-P$3-PadP3)") (class "Default")
      (node (ref "U$4") (pin "P3") (pinfunction "P$3_P3") (pintype "bidirectional"))
    )
    (net (code "86") (name "unconnected-(U$4-P$4-PadP4)") (class "Default")
      (node (ref "U$4") (pin "P4") (pinfunction "P$4_P4") (pintype "bidirectional"))
    )
    (net (code "87") (name "unconnected-(U$4-P$5-PadP5)") (class "Default")
      (node (ref "U$4") (pin "P5") (pinfunction "P$5_P5") (pintype "bidirectional"))
    )
  )
)
